# smd_missing_pulse_detector_pzt.net
KiCad netlist of a schematic drawn in EAGLE
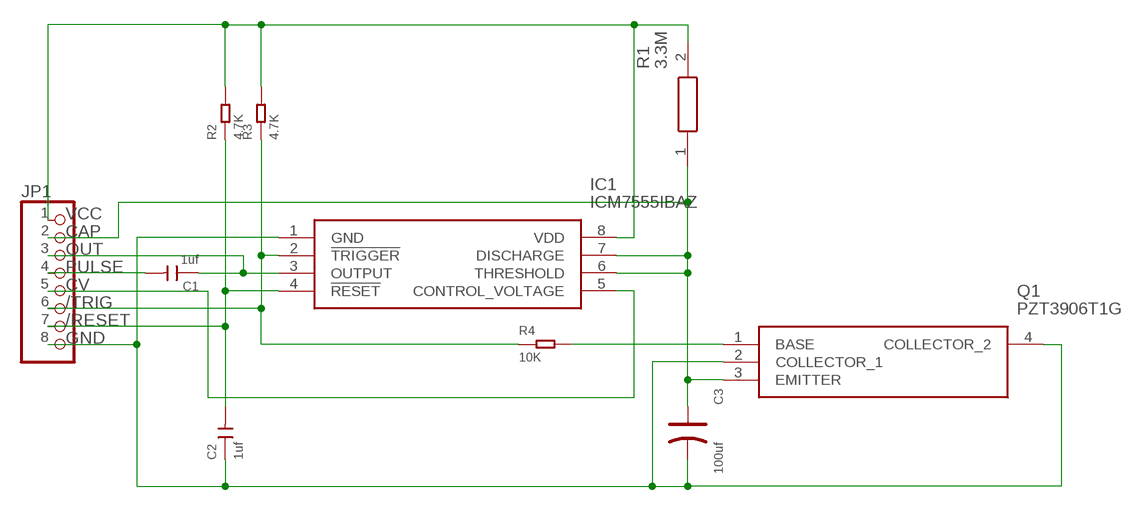
[diagram p0: schematic, sheet 1]

(export (version "E")
  (design (tool "Eeschema 10.0.6"))
  (components
    (comp (ref "C1")
      (value "1uf")
      (footprint "eagle-import:C0805")
      (fields (field (name "MPN") "CC0805KKX7R8BB105"))
      (libsource (lib "eagle-import") (part "CERAMIC-1UF-25V-10%-X7R(0805)"))
    )
    (comp (ref "C2")
      (value "1uf")
      (footprint "eagle-import:C0805")
      (fields (field (name "MPN") "CC0805KKX7R8BB105"))
      (libsource (lib "eagle-import") (part "CERAMIC-1UF-25V-10%-X7R(0805)"))
    )
    (comp (ref "C3")
      (value "100uf")
      (footprint "eagle-import:AVX-B")
      (fields (field (name "MPN") "TAJB107M010#NJ"))
      (libsource (lib "eagle-import") (part "TANTALUM-SMD-100UF-10V(AVX-B)"))
    )
    (comp (ref "IC1")
      (value "ICM7555IBAZ")
      (footprint "eagle-import:SOIC127P600X175-8N")
      (fields (field (name "MOUSER_PART_NUMBER") "968-ICM7555IBAZ"))
      (libsource (lib "eagle-import") (part "ICM7555IBAZ"))
    )
    (comp (ref "JP1")
      (value "PINHD-1X8")
      (footprint "eagle-import:1X08")
      (libsource (lib "eagle-import") (part "PINHD-1X8"))
    )
    (comp (ref "Q1")
      (value "PZT3906T1G")
      (footprint "eagle-import:SOT230P700X175-4N")
      (libsource (lib "eagle-import") (part "PZT3906T1G"))
    )
    (comp (ref "R1")
      (value "3.3M")
      (footprint "eagle-import:RESC1608X50N")
      (fields
        (field (name "ARROW_PART_NUMBER") "CRCW06033M30FKEA")
        (field (name "MOUSER_PART_NUMBER") "71-CRCW06033M30FKEA")
      )
      (libsource (lib "eagle-import") (part "CRCW06033M30FKEA"))
    )
    (comp (ref "R2")
      (value "4.7K")
      (footprint "eagle-import:R0603")
      (fields (field (name "MPN") "RC0603JR-074K7L"))
      (libsource (lib "eagle-import") (part "SMD-RES-4.7K-5%-1/10W(0603)"))
    )
    (comp (ref "R3")
      (value "4.7K")
      (footprint "eagle-import:R0603")
      (fields (field (name "MPN") "RC0603JR-074K7L"))
      (libsource (lib "eagle-import") (part "SMD-RES-4.7K-5%-1/10W(0603)"))
    )
    (comp (ref "R4")
      (value "10K")
      (footprint "eagle-import:R0603")
      (fields (field (name "MPN") "RC0603FR-0710KL"))
      (libsource (lib "eagle-import") (part "SMD-RES-10K-1%-1/10W(0603)"))
    )
  )
  (nets
    (net (code "1") (name "/CAP") (class "Default")
      (node (ref "C3") (pin "+") (pinfunction "+_+") (pintype "passive"))
      (node (ref "IC1") (pin "6") (pinfunction "THRESHOLD_6") (pintype "bidirectional"))
      (node (ref "IC1") (pin "7") (pinfunction "DISCHARGE_7") (pintype "bidirectional"))
      (node (ref "JP1") (pin "2") (pinfunction "2_2") (pintype "passive"))
      (node (ref "Q1") (pin "3") (pinfunction "EMITTER_3") (pintype "bidirectional"))
      (node (ref "R1") (pin "1") (pinfunction "1_1") (pintype "bidirectional"))
    )
    (net (code "2") (name "/CV") (class "Default")
      (node (ref "IC1") (pin "5") (pinfunction "CONTROL_VOLTAGE_5") (pintype "bidirectional"))
      (node (ref "JP1") (pin "5") (pinfunction "5_5") (pintype "passive"))
    )
    (net (code "3") (name "/GND") (class "Default")
      (node (ref "C2") (pin "1") (pinfunction "1_1") (pintype "passive"))
      (node (ref "C3") (pin "-") (pinfunction "-_-") (pintype "passive"))
      (node (ref "IC1") (pin "1") (pinfunction "GND_1") (pintype "bidirectional"))
      (node (ref "JP1") (pin "8") (pinfunction "8_8") (pintype "passive"))
      (node (ref "Q1") (pin "2") (pinfunction "COLLECTOR_1_2") (pintype "bidirectional"))
      (node (ref "Q1") (pin "4") (pinfunction "COLLECTOR_2_4") (pintype "bidirectional"))
    )
    (net (code "4") (name "/OUT") (class "Default")
      (node (ref "C1") (pin "1") (pinfunction "1_1") (pintype "passive"))
      (node (ref "IC1") (pin "3") (pinfunction "OUTPUT_3") (pintype "bidirectional"))
      (node (ref "JP1") (pin "3") (pinfunction "3_3") (pintype "passive"))
    )
    (net (code "5") (name "/PULSE") (class "Default")
      (node (ref "C1") (pin "2") (pinfunction "2_2") (pintype "passive"))
      (node (ref "JP1") (pin "4") (pinfunction "4_4") (pintype "passive"))
    )
    (net (code "6") (name "/VCC") (class "Default")
      (node (ref "IC1") (pin "8") (pinfunction "VDD_8") (pintype "bidirectional"))
      (node (ref "JP1") (pin "1") (pinfunction "1_1") (pintype "passive"))
      (node (ref "R1") (pin "2") (pinfunction "2_2") (pintype "bidirectional"))
      (node (ref "R2") (pin "2") (pinfunction "2_2") (pintype "passive"))
      (node (ref "R3") (pin "2") (pinfunction "2_2") (pintype "passive"))
    )
    (net (code "7") (name "/{slash}RESET") (class "Default")
      (node (ref "C2") (pin "2") (pinfunction "2_2") (pintype "passive"))
      (node (ref "IC1") (pin "4") (pinfunction "~{RESET}_4") (pintype "bidirectional"))
      (node (ref "JP1") (pin "7") (pinfunction "7_7") (pintype "passive"))
      (node (ref "R2") (pin "1") (pinfunction "1_1") (pintype "passive"))
    )
    (net (code "8") (name "/{slash}TRIG") (class "Default")
      (node (ref "IC1") (pin "2") (pinfunction "~{TRIGGER}_2") (pintype "bidirectional"))
      (node (ref "JP1") (pin "6") (pinfunction "6_6") (pintype "passive"))
      (node (ref "R3") (pin "1") (pinfunction "1_1") (pintype "passive"))
      (node (ref "R4") (pin "1") (pinfunction "1_1") (pintype "passive"))
    )
    (net (code "9") (name "Net-(Q1-BASE)") (class "Default")
      (node (ref "Q1") (pin "1") (pinfunction "BASE_1") (pintype "bidirectional"))
      (node (ref "R4") (pin "2") (pinfunction "2_2") (pintype "passive"))
    )
  )
)
